# NCS_Wireless_Bed_Unit_mcu.net
KiCad netlist of a schematic drawn in Altium Designer
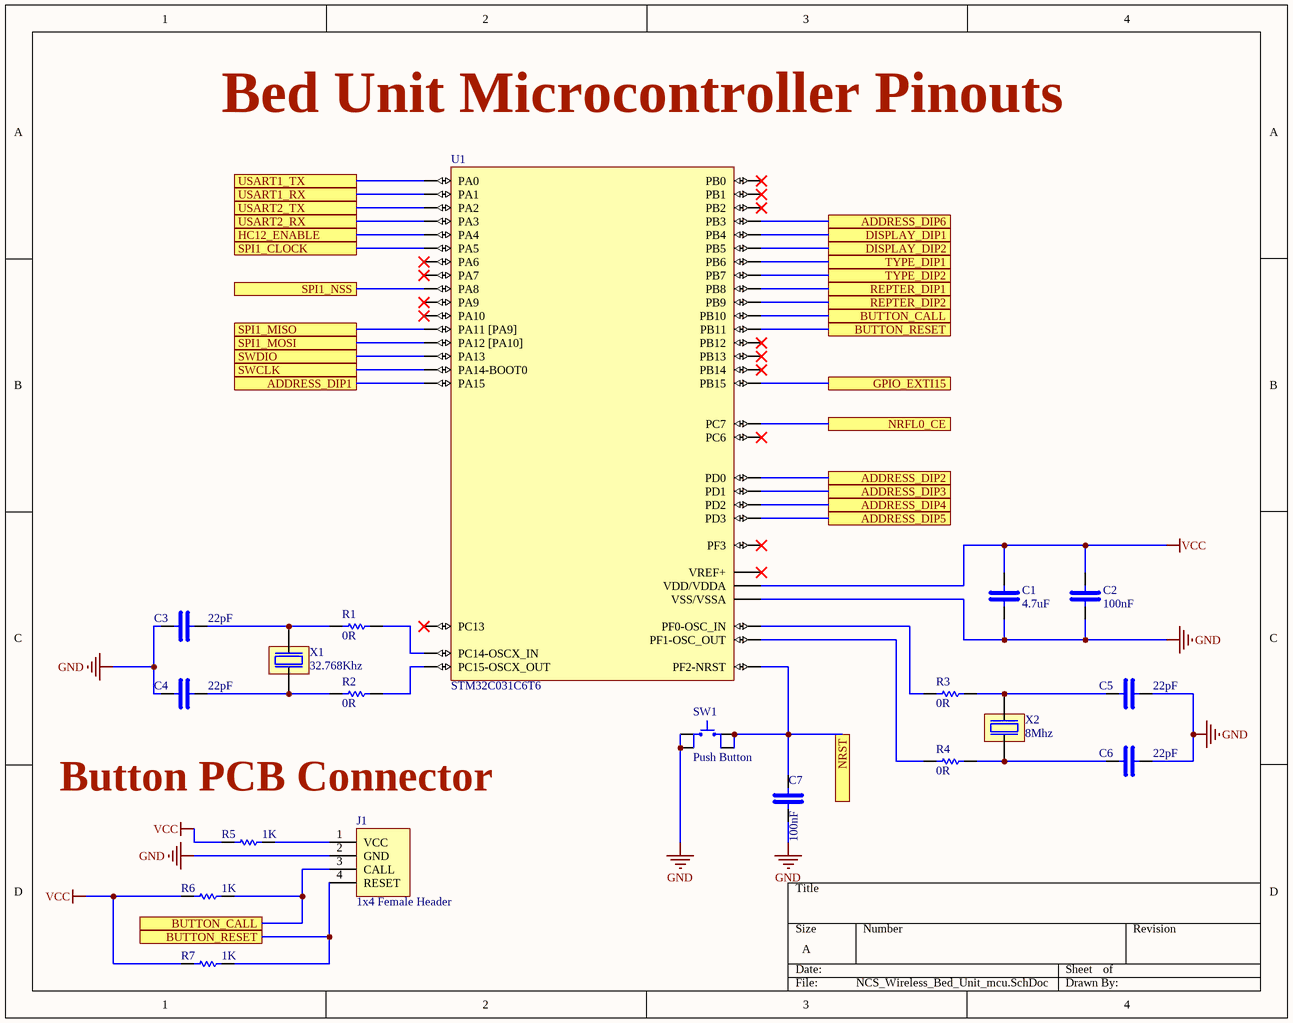
[diagram p0: NCS_Wireless_Bed_Unit_mcu.SchDoc]

(export (version "E")
  (design (tool "Eeschema 10.0.6"))
  (components
    (comp (ref "C1")
      (value "4.7uF")
      (footprint "C0805C209D3HACTU_2pF")
      (description "Multilayer Ceramic Capacitor, 4.7 uF, 25 V, ï¿½ 10%, X5R, 0805 [2012 Metric]")
      (fields
        (field (name "MANUFACTURER") "KEMET")
        (field (name "MANUFACTURER PART NUMBER") "C0805C475K3PACTU")
      )
      (libsource (lib "schlib") (part "C0805C475K3PACTU"))
    )
    (comp (ref "C2")
      (value "100nF")
      (footprint "C0805C104K3RACTU_100nF")
      (description "Multilayer Ceramic Capacitor, 0.1 uF, 25 V, ï¿½ 10%, X7R, 0805 [2012 Metric]")
      (fields
        (field (name "MANUFACTURER") "KEMET")
        (field (name "MANUFACTURER PART NUMBER") "C0805C104K3RACTU")
      )
      (libsource (lib "schlib") (part "C0805C104K3RACTU"))
    )
    (comp (ref "C3")
      (value "22pF")
      (footprint "C0805C209D3HACTU_2pF")
      (description "C0805C209D3HACTU_2pF")
      (fields
        (field (name "MANUFACTURER") "KEMET")
        (field (name "MANUFACTURER PART NUMBER") "C0805C209D3HACTU")
      )
      (libsource (lib "schlib") (part "C0805C209D3HACTU"))
    )
    (comp (ref "C4")
      (value "22pF")
      (footprint "C0805C209D3HACTU_2pF")
      (description "C0805C209D3HACTU_2pF")
      (fields
        (field (name "MANUFACTURER") "KEMET")
        (field (name "MANUFACTURER PART NUMBER") "C0805C209D3HACTU")
      )
      (libsource (lib "schlib") (part "C0805C209D3HACTU"))
    )
    (comp (ref "C5")
      (value "22pF")
      (footprint "C0805C209D3HACTU_2pF")
      (description "C0805C209D3HACTU_2pF")
      (fields
        (field (name "MANUFACTURER") "KEMET")
        (field (name "MANUFACTURER PART NUMBER") "C0805C209D3HACTU")
      )
      (libsource (lib "schlib") (part "C0805C209D3HACTU"))
    )
    (comp (ref "C6")
      (value "22pF")
      (footprint "C0805C209D3HACTU_2pF")
      (description "C0805C209D3HACTU_2pF")
      (fields
        (field (name "MANUFACTURER") "KEMET")
        (field (name "MANUFACTURER PART NUMBER") "C0805C209D3HACTU")
      )
      (libsource (lib "schlib") (part "C0805C209D3HACTU"))
    )
    (comp (ref "C7")
      (value "100nF")
      (footprint "C0805C104K3RACTU_100nF")
      (description "Multilayer Ceramic Capacitor, 0.1 uF, 25 V, ï¿½ 10%, X7R, 0805 [2012 Metric]")
      (fields
        (field (name "MANUFACTURER") "KEMET")
        (field (name "MANUFACTURER PART NUMBER") "C0805C104K3RACTU")
      )
      (libsource (lib "schlib") (part "C0805C104K3RACTU"))
    )
    (comp (ref "J1")
      (value "1x4 Female Header")
      (footprint "1x4 Female Socket")
      (description "Wafer: , Tin Overall, Straight w/ Type 1 Kinked End Pins, 1x4 Pos (4 pins)")
      (fields
        (field (name "MANUFACTURER") "Sullins")
        (field (name "MANUFACTURER PART NUMBER") "SWR201-NRTN-S04-SA-WH")
      )
      (libsource (lib "BSCU_SMD_lib") (part "SWR201-NRTN-S04-SA-WH"))
    )
    (comp (ref "R1")
      (value "0R")
      (footprint "RC0805JR-070RL")
      (description "GENERAL PURPOSE CHIP RESISTOR Metal Glaze/thick Film, 0.125W, 0ohm, Surface Mount, 0805")
      (fields
        (field (name "MANUFACTURER") "Yageo")
        (field (name "MANUFACTURER PART NUMBER") "RC0805JR-070RL")
      )
      (libsource (lib "schlib") (part "RC0805JR-070RL"))
    )
    (comp (ref "R2")
      (value "0R")
      (footprint "RC0805JR-070RL")
      (description "GENERAL PURPOSE CHIP RESISTOR Metal Glaze/thick Film, 0.125W, 0ohm, Surface Mount, 0805")
      (fields
        (field (name "MANUFACTURER") "Yageo")
        (field (name "MANUFACTURER PART NUMBER") "RC0805JR-070RL")
      )
      (libsource (lib "schlib") (part "RC0805JR-070RL"))
    )
    (comp (ref "R3")
      (value "0R")
      (footprint "RC0805JR-070RL")
      (description "GENERAL PURPOSE CHIP RESISTOR Metal Glaze/thick Film, 0.125W, 0ohm, Surface Mount, 0805")
      (fields
        (field (name "MANUFACTURER") "Yageo")
        (field (name "MANUFACTURER PART NUMBER") "RC0805JR-070RL")
      )
      (libsource (lib "schlib") (part "RC0805JR-070RL"))
    )
    (comp (ref "R4")
      (value "0R")
      (footprint "RC0805JR-070RL")
      (description "GENERAL PURPOSE CHIP RESISTOR Metal Glaze/thick Film, 0.125W, 0ohm, Surface Mount, 0805")
      (fields
        (field (name "MANUFACTURER") "Yageo")
        (field (name "MANUFACTURER PART NUMBER") "RC0805JR-070RL")
      )
      (libsource (lib "schlib") (part "RC0805JR-070RL"))
    )
    (comp (ref "R5")
      (value "1K")
      (footprint "AC0805FR-7W1KL")
      (description "SMD Chip Resistor, 1 kOhm, ± 1%, 250 mW, 0805 [2012 Metric], Thick Film, General Purpose")
      (fields
        (field (name "MANUFACTURER") "Yageo")
        (field (name "MANUFACTURER PART NUMBER") "AC0805FR-7W1KL")
      )
      (libsource (lib "schlib") (part "AC0805FR-7W1KL"))
    )
    (comp (ref "R6")
      (value "1K")
      (footprint "AC0805FR-7W1KL")
      (description "SMD Chip Resistor, 1 kOhm, ± 1%, 250 mW, 0805 [2012 Metric], Thick Film, General Purpose")
      (fields
        (field (name "MANUFACTURER") "Yageo")
        (field (name "MANUFACTURER PART NUMBER") "AC0805FR-7W1KL")
      )
      (libsource (lib "schlib") (part "AC0805FR-7W1KL"))
    )
    (comp (ref "R7")
      (value "1K")
      (footprint "AC0805FR-7W1KL")
      (description "SMD Chip Resistor, 1 kOhm, ± 1%, 250 mW, 0805 [2012 Metric], Thick Film, General Purpose")
      (fields
        (field (name "MANUFACTURER") "Yageo")
        (field (name "MANUFACTURER PART NUMBER") "AC0805FR-7W1KL")
      )
      (libsource (lib "schlib") (part "AC0805FR-7W1KL"))
    )
    (comp (ref "SW1")
      (value "Push Button")
      (footprint "PUSH BUTTON SMD")
      (libsource (lib "NCS_Wireless_Bed_Unit") (part "Tactile Switch SMD 4P 5.2x5.2x1.5mm - EVELTA"))
    )
    (comp (ref "U1")
      (value "STM32C031C6T6")
      (footprint "STM32C031C6T6-48N")
      (description "RISC Microcontroller, 32-Bit, FLASH, CORTEX-M4F CPU, 180MHz, CMOS, PBGA216")
      (fields (field (name "MANUFACTURER") "STMicroelectronics"))
      (libsource (lib "NCS_Wireless_Bed_Unit") (part "STM32C031C6T6"))
    )
    (comp (ref "X1")
      (value "32.768Khz")
      (footprint "32.768KHz")
      (libsource (lib "NCS_Wireless_Bed_Unit") (part "32.768 Khz RTC Crystal T38-SUNROM"))
    )
    (comp (ref "X2")
      (value "8Mhz")
      (footprint "8Mhz Crystal")
      (libsource (lib "NCS_Wireless_Bed_Unit") (part "8 Mhz Crystal HC-49US-SUNROM"))
    )
  )
  (nets
    (net (code "1") (name "/ADDRESS_DIP1") (class "Default")
      (node (ref "U1") (pin "37") (pinfunction "PA15_37") (pintype "bidirectional"))
    )
    (net (code "2") (name "/ADDRESS_DIP2") (class "Default")
      (node (ref "U1") (pin "38") (pinfunction "PD0_38") (pintype "bidirectional"))
    )
    (net (code "3") (name "/ADDRESS_DIP3") (class "Default")
      (node (ref "U1") (pin "39") (pinfunction "PD1_39") (pintype "bidirectional"))
    )
    (net (code "4") (name "/ADDRESS_DIP4") (class "Default")
      (node (ref "U1") (pin "40") (pinfunction "PD2_40") (pintype "bidirectional"))
    )
    (net (code "5") (name "/ADDRESS_DIP5") (class "Default")
      (node (ref "U1") (pin "41") (pinfunction "PD3_41") (pintype "bidirectional"))
    )
    (net (code "6") (name "/ADDRESS_DIP6") (class "Default")
      (node (ref "U1") (pin "42") (pinfunction "PB3_42") (pintype "bidirectional"))
    )
    (net (code "7") (name "/BUTTON_CALL") (class "Default")
      (node (ref "J1") (pin "3") (pinfunction "CALL_3") (pintype "passive"))
      (node (ref "R6") (pin "2") (pinfunction "2_2") (pintype "passive"))
      (node (ref "U1") (pin "22") (pinfunction "PB10_22") (pintype "bidirectional"))
    )
    (net (code "8") (name "/BUTTON_RESET") (class "Default")
      (node (ref "J1") (pin "4") (pinfunction "RESET_4") (pintype "passive"))
      (node (ref "R7") (pin "2") (pinfunction "2_2") (pintype "passive"))
      (node (ref "U1") (pin "23") (pinfunction "PB11_23") (pintype "bidirectional"))
    )
    (net (code "9") (name "/DISPLAY_DIP1") (class "Default")
      (node (ref "U1") (pin "43") (pinfunction "PB4_43") (pintype "bidirectional"))
    )
    (net (code "10") (name "/DISPLAY_DIP2") (class "Default")
      (node (ref "U1") (pin "44") (pinfunction "PB5_44") (pintype "bidirectional"))
    )
    (net (code "11") (name "/GPIO_EXTI15") (class "Default")
      (node (ref "U1") (pin "27") (pinfunction "PB15_27") (pintype "bidirectional"))
    )
    (net (code "12") (name "/HC12_ENABLE") (class "Default")
      (node (ref "U1") (pin "15") (pinfunction "PA4_15") (pintype "bidirectional"))
    )
    (net (code "13") (name "/NRFL0_CE") (class "Default")
      (node (ref "U1") (pin "31") (pinfunction "PC7_31") (pintype "bidirectional"))
    )
    (net (code "14") (name "/NRST") (class "Default")
      (node (ref "C7") (pin "2") (pinfunction "2_2") (pintype "passive"))
      (node (ref "SW1") (pin "3") (pinfunction "3_3") (pintype "passive"))
      (node (ref "SW1") (pin "4") (pinfunction "4_4") (pintype "passive"))
      (node (ref "U1") (pin "10") (pinfunction "PF2-NRST_10") (pintype "bidirectional"))
    )
    (net (code "15") (name "/REPTER_DIP1") (class "Default")
      (node (ref "U1") (pin "47") (pinfunction "PB8_47") (pintype "bidirectional"))
    )
    (net (code "16") (name "/REPTER_DIP2") (class "Default")
      (node (ref "U1") (pin "48") (pinfunction "PB9_48") (pintype "bidirectional"))
    )
    (net (code "17") (name "/SPI1_CLOCK") (class "Default")
      (node (ref "U1") (pin "16") (pinfunction "PA5_16") (pintype "bidirectional"))
    )
    (net (code "18") (name "/SPI1_MISO") (class "Default")
      (node (ref "U1") (pin "33") (pinfunction "PA11_[PA9]_33") (pintype "bidirectional"))
    )
    (net (code "19") (name "/SPI1_MOSI") (class "Default")
      (node (ref "U1") (pin "34") (pinfunction "PA12_[PA10]_34") (pintype "bidirectional"))
    )
    (net (code "20") (name "/SPI1_NSS") (class "Default")
      (node (ref "U1") (pin "28") (pinfunction "PA8_28") (pintype "bidirectional"))
    )
    (net (code "21") (name "/SWCLK") (class "Default")
      (node (ref "U1") (pin "36") (pinfunction "PA14-BOOT0_36") (pintype "bidirectional"))
    )
    (net (code "22") (name "/SWDIO") (class "Default")
      (node (ref "U1") (pin "35") (pinfunction "PA13_35") (pintype "bidirectional"))
    )
    (net (code "23") (name "/TYPE_DIP1") (class "Default")
      (node (ref "U1") (pin "45") (pinfunction "PB6_45") (pintype "bidirectional"))
    )
    (net (code "24") (name "/TYPE_DIP2") (class "Default")
      (node (ref "U1") (pin "46") (pinfunction "PB7_46") (pintype "bidirectional"))
    )
    (net (code "25") (name "/USART1_RX") (class "Default")
      (node (ref "U1") (pin "12") (pinfunction "PA1_12") (pintype "bidirectional"))
    )
    (net (code "26") (name "/USART1_TX") (class "Default")
      (node (ref "U1") (pin "11") (pinfunction "PA0_11") (pintype "bidirectional"))
    )
    (net (code "27") (name "/USART2_RX") (class "Default")
      (node (ref "U1") (pin "14") (pinfunction "PA3_14") (pintype "bidirectional"))
    )
    (net (code "28") (name "/USART2_TX") (class "Default")
      (node (ref "U1") (pin "13") (pinfunction "PA2_13") (pintype "bidirectional"))
    )
    (net (code "29") (name "GND") (class "Default")
      (node (ref "C1") (pin "1") (pinfunction "1_1") (pintype "passive"))
      (node (ref "C2") (pin "1") (pinfunction "1_1") (pintype "passive"))
      (node (ref "C3") (pin "2") (pinfunction "2_2") (pintype "passive"))
      (node (ref "C4") (pin "2") (pinfunction "2_2") (pintype "passive"))
      (node (ref "C5") (pin "1") (pinfunction "1_1") (pintype "passive"))
      (node (ref "C6") (pin "1") (pinfunction "1_1") (pintype "passive"))
      (node (ref "C7") (pin "1") (pinfunction "1_1") (pintype "passive"))
      (node (ref "J1") (pin "2") (pinfunction "GND_2") (pintype "passive"))
      (node (ref "SW1") (pin "1") (pinfunction "1_1") (pintype "passive"))
      (node (ref "SW1") (pin "2") (pinfunction "2_2") (pintype "passive"))
      (node (ref "U1") (pin "7") (pinfunction "VSS/VSSA_7") (pintype "power_in"))
    )
    (net (code "30") (name "Net-(C3-Pad1)") (class "Default")
      (node (ref "C3") (pin "1") (pinfunction "1_1") (pintype "passive"))
      (node (ref "R1") (pin "1") (pinfunction "1_1") (pintype "passive"))
      (node (ref "X1") (pin "2") (pinfunction "2_2") (pintype "passive"))
    )
    (net (code "31") (name "Net-(C4-Pad1)") (class "Default")
      (node (ref "C4") (pin "1") (pinfunction "1_1") (pintype "passive"))
      (node (ref "R2") (pin "1") (pinfunction "1_1") (pintype "passive"))
      (node (ref "X1") (pin "1") (pinfunction "1_1") (pintype "passive"))
    )
    (net (code "32") (name "Net-(C5-Pad2)") (class "Default")
      (node (ref "C5") (pin "2") (pinfunction "2_2") (pintype "passive"))
      (node (ref "R3") (pin "2") (pinfunction "2_2") (pintype "passive"))
      (node (ref "X2") (pin "2") (pinfunction "2_2") (pintype "passive"))
    )
    (net (code "33") (name "Net-(C6-Pad2)") (class "Default")
      (node (ref "C6") (pin "2") (pinfunction "2_2") (pintype "passive"))
      (node (ref "R4") (pin "2") (pinfunction "2_2") (pintype "passive"))
      (node (ref "X2") (pin "1") (pinfunction "1_1") (pintype "passive"))
    )
    (net (code "34") (name "Net-(J1-VCC)") (class "Default")
      (node (ref "J1") (pin "1") (pinfunction "VCC_1") (pintype "passive"))
      (node (ref "R5") (pin "2") (pinfunction "2_2") (pintype "passive"))
    )
    (net (code "35") (name "Net-(U1-PC14-OSCX_IN)") (class "Default")
      (node (ref "R1") (pin "2") (pinfunction "2_2") (pintype "passive"))
      (node (ref "U1") (pin "2") (pinfunction "PC14-OSCX_IN_2") (pintype "bidirectional"))
    )
    (net (code "36") (name "Net-(U1-PC15-OSCX_OUT)") (class "Default")
      (node (ref "R2") (pin "2") (pinfunction "2_2") (pintype "passive"))
      (node (ref "U1") (pin "3") (pinfunction "PC15-OSCX_OUT_3") (pintype "bidirectional"))
    )
    (net (code "37") (name "Net-(U1-PF0-OSC_IN)") (class "Default")
      (node (ref "R3") (pin "1") (pinfunction "1_1") (pintype "passive"))
      (node (ref "U1") (pin "8") (pinfunction "PF0-OSC_IN_8") (pintype "bidirectional"))
    )
    (net (code "38") (name "Net-(U1-PF1-OSC_OUT)") (class "Default")
      (node (ref "R4") (pin "1") (pinfunction "1_1") (pintype "passive"))
      (node (ref "U1") (pin "9") (pinfunction "PF1-OSC_OUT_9") (pintype "bidirectional"))
    )
    (net (code "39") (name "VCC") (class "Default")
      (node (ref "C1") (pin "2") (pinfunction "2_2") (pintype "passive"))
      (node (ref "C2") (pin "2") (pinfunction "2_2") (pintype "passive"))
      (node (ref "R5") (pin "1") (pinfunction "1_1") (pintype "passive"))
      (node (ref "R6") (pin "1") (pinfunction "1_1") (pintype "passive"))
      (node (ref "R7") (pin "1") (pinfunction "1_1") (pintype "passive"))
      (node (ref "U1") (pin "6") (pinfunction "VDD/VDDA_6") (pintype "power_in"))
    )
    (net (code "40") (name "unconnected-(U1-PA6-Pad17)") (class "Default")
      (node (ref "U1") (pin "17") (pinfunction "PA6_17") (pintype "bidirectional+no_connect"))
    )
    (net (code "41") (name "unconnected-(U1-PA7-Pad18)") (class "Default")
      (node (ref "U1") (pin "18") (pinfunction "PA7_18") (pintype "bidirectional+no_connect"))
    )
    (net (code "42") (name "unconnected-(U1-PA9-Pad29)") (class "Default")
      (node (ref "U1") (pin "29") (pinfunction "PA9_29") (pintype "bidirectional+no_connect"))
    )
    (net (code "43") (name "unconnected-(U1-PA10-Pad32)") (class "Default")
      (node (ref "U1") (pin "32") (pinfunction "PA10_32") (pintype "bidirectional+no_connect"))
    )
    (net (code "44") (name "unconnected-(U1-PB0-Pad19)") (class "Default")
      (node (ref "U1") (pin "19") (pinfunction "PB0_19") (pintype "bidirectional+no_connect"))
    )
    (net (code "45") (name "unconnected-(U1-PB1-Pad20)") (class "Default")
      (node (ref "U1") (pin "20") (pinfunction "PB1_20") (pintype "bidirectional+no_connect"))
    )
    (net (code "46") (name "unconnected-(U1-PB2-Pad21)") (class "Default")
      (node (ref "U1") (pin "21") (pinfunction "PB2_21") (pintype "bidirectional+no_connect"))
    )
    (net (code "47") (name "unconnected-(U1-PB12-Pad24)") (class "Default")
      (node (ref "U1") (pin "24") (pinfunction "PB12_24") (pintype "bidirectional+no_connect"))
    )
    (net (code "48") (name "unconnected-(U1-PB13-Pad25)") (class "Default")
      (node (ref "U1") (pin "25") (pinfunction "PB13_25") (pintype "bidirectional+no_connect"))
    )
    (net (code "49") (name "unconnected-(U1-PB14-Pad26)") (class "Default")
      (node (ref "U1") (pin "26") (pinfunction "PB14_26") (pintype "bidirectional+no_connect"))
    )
    (net (code "50") (name "unconnected-(U1-PC6-Pad30)") (class "Default")
      (node (ref "U1") (pin "30") (pinfunction "PC6_30") (pintype "bidirectional+no_connect"))
    )
    (net (code "51") (name "unconnected-(U1-PC13-Pad1)") (class "Default")
      (node (ref "U1") (pin "1") (pinfunction "PC13_1") (pintype "bidirectional+no_connect"))
    )
    (net (code "52") (name "unconnected-(U1-PF3-Pad4)") (class "Default")
      (node (ref "U1") (pin "4") (pinfunction "PF3_4") (pintype "bidirectional+no_connect"))
    )
    (net (code "53") (name "unconnected-(U1-VREF+-Pad5)") (class "Default")
      (node (ref "U1") (pin "5") (pinfunction "VREF+_5") (pintype "power_in+no_connect"))
    )
  )
)
